# POWER.net
KiCad netlist of a schematic drawn in Altium Designer
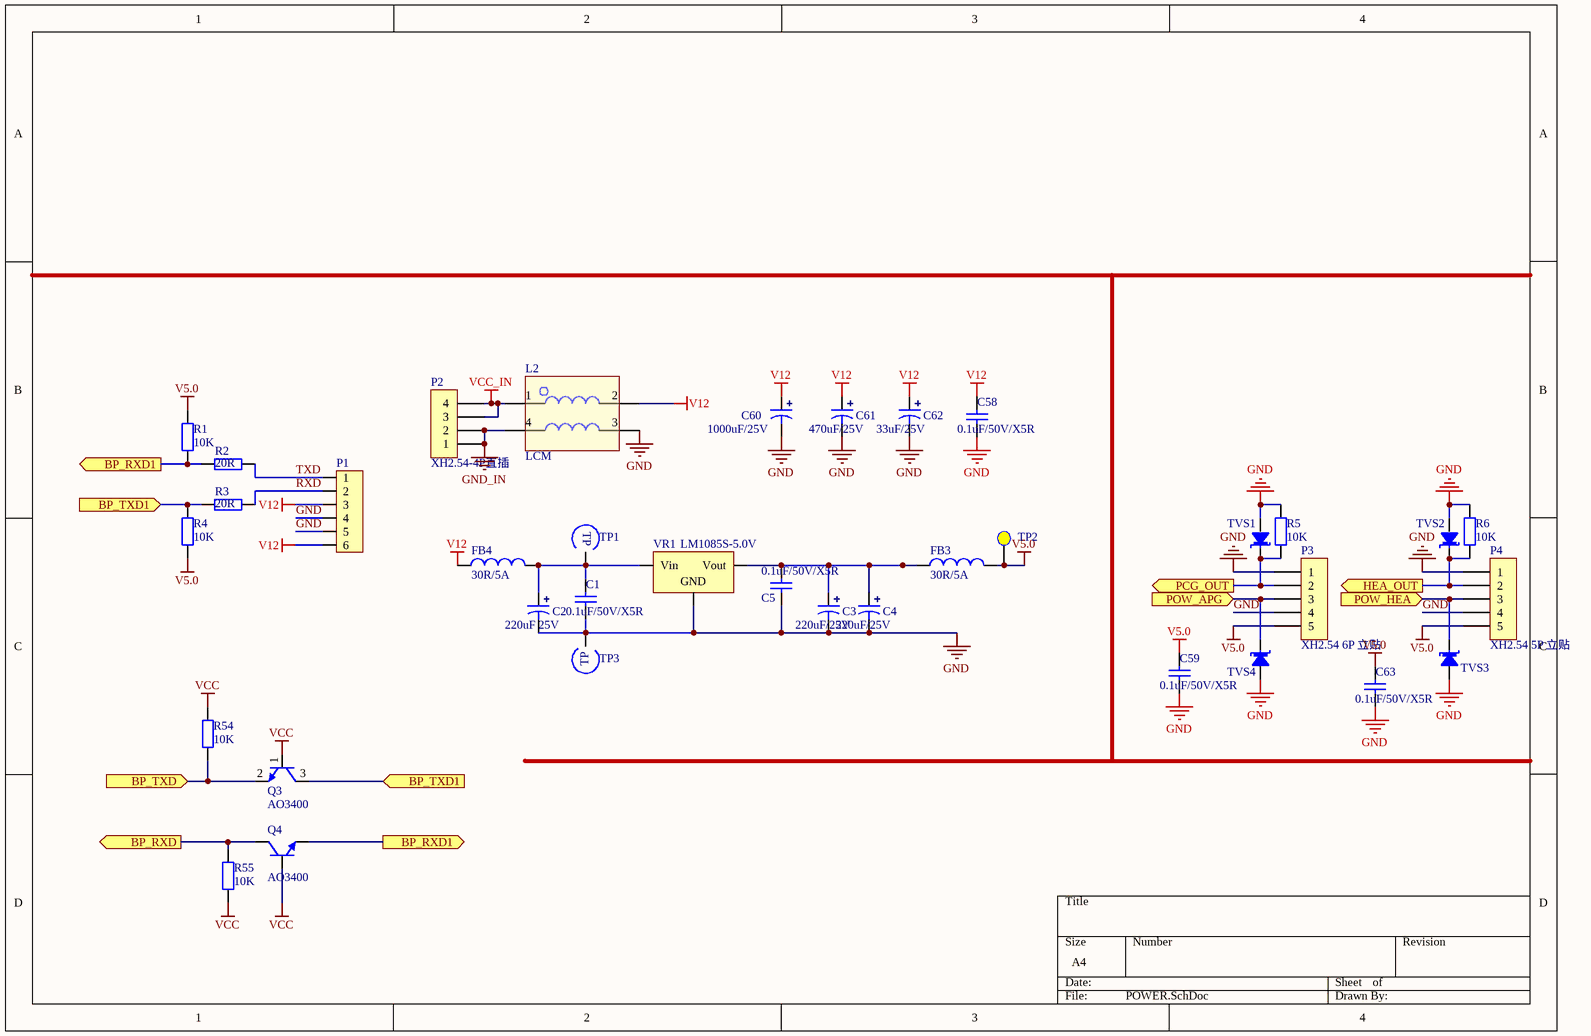
[diagram p0: POWER.SchDoc]

(export (version "E")
  (design (tool "Eeschema 10.0.6"))
  (components
    (comp (ref "C1")
      (value "0.1uF/50V/X5R")
      (footprint "SMD-0603C")
      (description "贴片电容 20%")
      (libsource (lib "XiaoyI") (part "CAP4"))
    )
    (comp (ref "C2")
      (value "220uF 25V")
      (footprint "SMD-6.3*7.7")
      (description "电解电容")
      (libsource (lib "XiaoyI") (part "CAP2"))
    )
    (comp (ref "C3")
      (value "220uF/25V")
      (footprint "SMD-6.3*7.7")
      (description "电解电容")
      (libsource (lib "XiaoyI") (part "CAP2"))
    )
    (comp (ref "C4")
      (value "220uF/25V")
      (footprint "SMD-6.3*7.7")
      (description "电解电容")
      (libsource (lib "XiaoyI") (part "CAP2"))
    )
    (comp (ref "C5")
      (value "0.1uF/50V/X5R")
      (footprint "SMD-0603C")
      (description "贴片电容 20%")
      (libsource (lib "XiaoyI") (part "CAP4"))
    )
    (comp (ref "C58")
      (value "0.1uF/50V/X5R")
      (footprint "SMD-0603C")
      (description "贴片电容 20%")
      (libsource (lib "XiaoyI") (part "CAP4"))
    )
    (comp (ref "C59")
      (value "0.1uF/50V/X5R")
      (footprint "SMD-0603C")
      (description "贴片电容 20%")
      (libsource (lib "XiaoyI") (part "CAP4"))
    )
    (comp (ref "C60")
      (value "1000uF/25V")
      (footprint "10*16")
      (description "电解电容")
      (libsource (lib "XiaoyI") (part "CAP2"))
    )
    (comp (ref "C61")
      (value "470uF/25V")
      (footprint "8*12")
      (description "电解电容")
      (libsource (lib "XiaoyI") (part "CAP2"))
    )
    (comp (ref "C62")
      (value "33uF/25V")
      (footprint "5*7")
      (description "电解电容")
      (libsource (lib "XiaoyI") (part "CAP2"))
    )
    (comp (ref "C63")
      (value "0.1uF/50V/X5R")
      (footprint "SMD-0603C")
      (description "贴片电容 20%")
      (libsource (lib "XiaoyI") (part "CAP4"))
    )
    (comp (ref "FB3")
      (value "30R/5A")
      (footprint "0603r")
      (description "Inductor")
      (fields (field (name "PUBLISHER") "Altium Limited"))
      (libsource (lib "Miscellaneous Devices") (part "Inductor"))
    )
    (comp (ref "FB4")
      (value "30R/5A")
      (footprint "0603r")
      (description "Inductor")
      (fields (field (name "PUBLISHER") "Altium Limited"))
      (libsource (lib "Miscellaneous Devices") (part "Inductor"))
    )
    (comp (ref "L2") (value "LCM") (footprint "LCM") (libsource (lib "stm32") (part "LCM")))
    (comp (ref "P1")
      (value "XH2.54 6P 立贴")
      (footprint "XH-2.54-6P-LI")
      (description "血压计接口")
      (libsource (lib "ABB") (part "SIP-6"))
    )
    (comp (ref "P2") (value "XH2.54-4P直插") (footprint "4X2.54MMZ") (libsource (lib "ABB") (part "SIP-4")))
    (comp (ref "P3")
      (value "XH2.54 6P 立贴")
      (footprint "XH-2.54-5P-LI")
      (description "颈动脉传感器接口")
      (libsource (lib "ABB") (part "SIP-5"))
    )
    (comp (ref "P4")
      (value "XH2.54 5P 立贴")
      (footprint "XH-2.54-5P-LI")
      (description "心音传感器接口")
      (libsource (lib "ABB") (part "SIP-5"))
    )
    (comp (ref "Q3")
      (value "AO3400")
      (footprint "SOT-23")
      (description "NPN")
      (libsource (lib "") (part "NPN-1_1"))
    )
    (comp (ref "Q4")
      (value "AO3400")
      (footprint "SOT-23")
      (description "NPN")
      (libsource (lib "XiaoyI") (part "NPN-1"))
    )
    (comp (ref "R1")
      (value "10K")
      (footprint "SMD-0603")
      (description "贴片电阻 1%")
      (libsource (lib "") (part "RES2_2"))
    )
    (comp (ref "R2")
      (value "20R")
      (footprint "SMD-0603")
      (description "贴片电阻 1%")
      (libsource (lib "") (part "RES2_1"))
    )
    (comp (ref "R3")
      (value "20R")
      (footprint "SMD-0603")
      (description "贴片电阻 1%")
      (libsource (lib "") (part "RES2_1"))
    )
    (comp (ref "R4")
      (value "10K")
      (footprint "SMD-0603")
      (description "贴片电阻 1%")
      (libsource (lib "") (part "RES2_2"))
    )
    (comp (ref "R5")
      (value "10K")
      (footprint "SMD-0603")
      (description "贴片电阻 1%")
      (libsource (lib "") (part "RES2_2"))
    )
    (comp (ref "R6")
      (value "10K")
      (footprint "SMD-0603")
      (description "贴片电阻 1%")
      (libsource (lib "") (part "RES2_2"))
    )
    (comp (ref "R54")
      (value "10K")
      (footprint "SMD-0603")
      (description "贴片电阻 1%")
      (libsource (lib "XiaoyI") (part "RES2"))
    )
    (comp (ref "R55")
      (value "10K")
      (footprint "SMD-0603")
      (description "贴片电阻 1%")
      (libsource (lib "XiaoyI") (part "RES2"))
    )
    (comp (ref "TP1")
      (value "TP")
      (footprint "TP")
      (description "测试点")
      (libsource (lib "XiaoyI") (part "TP-1"))
    )
    (comp (ref "TP2")
      (value "TP")
      (footprint "TP")
      (description "测试点")
      (libsource (lib "ABB") (part "TP_POINT"))
    )
    (comp (ref "TP3")
      (value "TP")
      (footprint "TP")
      (description "测试点")
      (libsource (lib "XiaoyI") (part "TP-1"))
    )
    (comp (ref "TVS1")
      (value "TVS-S")
      (footprint "SOD-323")
      (description "单向TVS")
      (libsource (lib "XiaoyI") (part "TVS-S"))
    )
    (comp (ref "TVS2")
      (value "TVS-S")
      (footprint "SOD-323")
      (description "单向TVS")
      (libsource (lib "XiaoyI") (part "TVS-S"))
    )
    (comp (ref "TVS3")
      (value "TVS-S")
      (footprint "SOD-323")
      (description "单向TVS")
      (libsource (lib "") (part "TVS-S_1"))
    )
    (comp (ref "TVS4")
      (value "TVS-S")
      (footprint "SOD-323")
      (description "单向TVS")
      (libsource (lib "") (part "TVS-S_1"))
    )
    (comp (ref "VR1")
      (value "LM1085S-5.0V")
      (footprint "TO-263-3")
      (description "三端稳压器")
      (libsource (lib "XiaoyI") (part "LM1117"))
    )
  )
  (nets
    (net (code "1") (name "/BP_RXD") (class "Default")
      (node (ref "Q4") (pin "3") (pinfunction "C_3") (pintype "passive"))
      (node (ref "R55") (pin "2") (pinfunction "2_2") (pintype "passive"))
    )
    (net (code "2") (name "/BP_RXD1") (class "Default")
      (node (ref "Q4") (pin "2") (pinfunction "E_2") (pintype "passive"))
      (node (ref "R1") (pin "2") (pinfunction "2_2") (pintype "passive"))
      (node (ref "R2") (pin "2") (pinfunction "2_2") (pintype "passive"))
    )
    (net (code "3") (name "/BP_TXD") (class "Default")
      (node (ref "Q3") (pin "2") (pinfunction "E_2") (pintype "passive"))
      (node (ref "R54") (pin "1") (pinfunction "1_1") (pintype "passive"))
    )
    (net (code "4") (name "/BP_TXD1") (class "Default")
      (node (ref "Q3") (pin "3") (pinfunction "C_3") (pintype "passive"))
      (node (ref "R3") (pin "2") (pinfunction "2_2") (pintype "passive"))
      (node (ref "R4") (pin "1") (pinfunction "1_1") (pintype "passive"))
    )
    (net (code "5") (name "/HEA_OUT") (class "Default")
      (node (ref "P4") (pin "2") (pinfunction "2_2") (pintype "passive"))
      (node (ref "R6") (pin "2") (pinfunction "2_2") (pintype "passive"))
      (node (ref "TVS2") (pin "2") (pinfunction "B_2") (pintype "passive"))
    )
    (net (code "6") (name "/PCG_OUT") (class "Default")
      (node (ref "P3") (pin "2") (pinfunction "2_2") (pintype "passive"))
      (node (ref "R5") (pin "2") (pinfunction "2_2") (pintype "passive"))
      (node (ref "TVS1") (pin "2") (pinfunction "B_2") (pintype "passive"))
    )
    (net (code "7") (name "/POW_APG") (class "Default")
      (node (ref "P3") (pin "3") (pinfunction "3_3") (pintype "passive"))
      (node (ref "TVS4") (pin "2") (pinfunction "B_2") (pintype "passive"))
    )
    (net (code "8") (name "/POW_HEA") (class "Default")
      (node (ref "P4") (pin "3") (pinfunction "3_3") (pintype "passive"))
      (node (ref "TVS3") (pin "2") (pinfunction "B_2") (pintype "passive"))
    )
    (net (code "9") (name "/RXD") (class "Default")
      (node (ref "P1") (pin "2") (pinfunction "2_2") (pintype "passive"))
      (node (ref "R3") (pin "1") (pinfunction "1_1") (pintype "passive"))
    )
    (net (code "10") (name "/TXD") (class "Default")
      (node (ref "P1") (pin "1") (pinfunction "1_1") (pintype "passive"))
      (node (ref "R2") (pin "1") (pinfunction "1_1") (pintype "passive"))
    )
    (net (code "11") (name "GND") (class "Default")
      (node (ref "C1") (pin "1") (pinfunction "1_1") (pintype "passive"))
      (node (ref "C2") (pin "2") (pinfunction "2_2") (pintype "passive"))
      (node (ref "C3") (pin "2") (pinfunction "2_2") (pintype "passive"))
      (node (ref "C4") (pin "2") (pinfunction "2_2") (pintype "passive"))
      (node (ref "C5") (pin "1") (pinfunction "1_1") (pintype "passive"))
      (node (ref "C58") (pin "1") (pinfunction "1_1") (pintype "passive"))
      (node (ref "C59") (pin "1") (pinfunction "1_1") (pintype "passive"))
      (node (ref "C60") (pin "2") (pinfunction "2_2") (pintype "passive"))
      (node (ref "C61") (pin "2") (pinfunction "2_2") (pintype "passive"))
      (node (ref "C62") (pin "2") (pinfunction "2_2") (pintype "passive"))
      (node (ref "C63") (pin "1") (pinfunction "1_1") (pintype "passive"))
      (node (ref "L2") (pin "3") (pintype "passive"))
      (node (ref "P1") (pin "4") (pinfunction "4_4") (pintype "passive"))
      (node (ref "P1") (pin "5") (pinfunction "5_5") (pintype "passive"))
      (node (ref "P3") (pin "1") (pinfunction "1_1") (pintype "passive"))
      (node (ref "P3") (pin "4") (pinfunction "4_4") (pintype "passive"))
      (node (ref "P4") (pin "1") (pinfunction "1_1") (pintype "passive"))
      (node (ref "P4") (pin "4") (pinfunction "4_4") (pintype "passive"))
      (node (ref "R5") (pin "1") (pinfunction "1_1") (pintype "passive"))
      (node (ref "R6") (pin "1") (pinfunction "1_1") (pintype "passive"))
      (node (ref "TP3") (pin "1") (pinfunction "1_1") (pintype "passive"))
      (node (ref "TVS1") (pin "1") (pinfunction "A_1") (pintype "passive"))
      (node (ref "TVS2") (pin "1") (pinfunction "A_1") (pintype "passive"))
      (node (ref "TVS3") (pin "1") (pinfunction "A_1") (pintype "passive"))
      (node (ref "TVS4") (pin "1") (pinfunction "A_1") (pintype "passive"))
      (node (ref "VR1") (pin "1") (pinfunction "GND_1") (pintype "passive"))
    )
    (net (code "12") (name "GND_IN") (class "Default")
      (node (ref "L2") (pin "4") (pintype "passive"))
      (node (ref "P2") (pin "1") (pinfunction "1_1") (pintype "passive"))
      (node (ref "P2") (pin "2") (pinfunction "2_2") (pintype "passive"))
    )
    (net (code "13") (name "Net-(VR1-Vin)") (class "Default")
      (node (ref "C1") (pin "2") (pinfunction "2_2") (pintype "passive"))
      (node (ref "C2") (pin "1") (pinfunction "1_1") (pintype "passive"))
      (node (ref "FB4") (pin "2") (pinfunction "2_2") (pintype "passive"))
      (node (ref "TP1") (pin "1") (pinfunction "1_1") (pintype "passive"))
      (node (ref "VR1") (pin "3") (pinfunction "Vin_3") (pintype "passive"))
    )
    (net (code "14") (name "Net-(VR1-Vout)") (class "Default")
      (node (ref "C3") (pin "1") (pinfunction "1_1") (pintype "passive"))
      (node (ref "C4") (pin "1") (pinfunction "1_1") (pintype "passive"))
      (node (ref "C5") (pin "2") (pinfunction "2_2") (pintype "passive"))
      (node (ref "FB3") (pin "1") (pinfunction "1_1") (pintype "passive"))
      (node (ref "VR1") (pin "2") (pinfunction "Vout_2") (pintype "passive"))
    )
    (net (code "15") (name "V5.0") (class "Default")
      (node (ref "C59") (pin "2") (pinfunction "2_2") (pintype "passive"))
      (node (ref "C63") (pin "2") (pinfunction "2_2") (pintype "passive"))
      (node (ref "FB3") (pin "2") (pinfunction "2_2") (pintype "passive"))
      (node (ref "P3") (pin "5") (pinfunction "5_5") (pintype "passive"))
      (node (ref "P4") (pin "5") (pinfunction "5_5") (pintype "passive"))
      (node (ref "R1") (pin "1") (pinfunction "1_1") (pintype "passive"))
      (node (ref "R4") (pin "2") (pinfunction "2_2") (pintype "passive"))
      (node (ref "TP2") (pin "1") (pinfunction "TP_1") (pintype "power_in"))
    )
    (net (code "16") (name "V12") (class "Default")
      (node (ref "C58") (pin "2") (pinfunction "2_2") (pintype "passive"))
      (node (ref "C60") (pin "1") (pinfunction "1_1") (pintype "passive"))
      (node (ref "C61") (pin "1") (pinfunction "1_1") (pintype "passive"))
      (node (ref "C62") (pin "1") (pinfunction "1_1") (pintype "passive"))
      (node (ref "FB4") (pin "1") (pinfunction "1_1") (pintype "passive"))
      (node (ref "L2") (pin "2") (pintype "passive"))
      (node (ref "P1") (pin "3") (pinfunction "3_3") (pintype "passive"))
      (node (ref "P1") (pin "6") (pinfunction "6_6") (pintype "passive"))
    )
    (net (code "17") (name "VCC") (class "Default")
      (node (ref "Q3") (pin "1") (pinfunction "B_1") (pintype "passive"))
      (node (ref "Q4") (pin "1") (pinfunction "B_1") (pintype "passive"))
      (node (ref "R54") (pin "2") (pinfunction "2_2") (pintype "passive"))
      (node (ref "R55") (pin "1") (pinfunction "1_1") (pintype "passive"))
    )
    (net (code "18") (name "VCC_IN") (class "Default")
      (node (ref "L2") (pin "1") (pintype "passive"))
      (node (ref "P2") (pin "3") (pinfunction "3_3") (pintype "passive"))
      (node (ref "P2") (pin "4") (pinfunction "4_4") (pintype "passive"))
    )
  )
)
